# dimmer.net
KiCad netlist of a schematic drawn in EAGLE
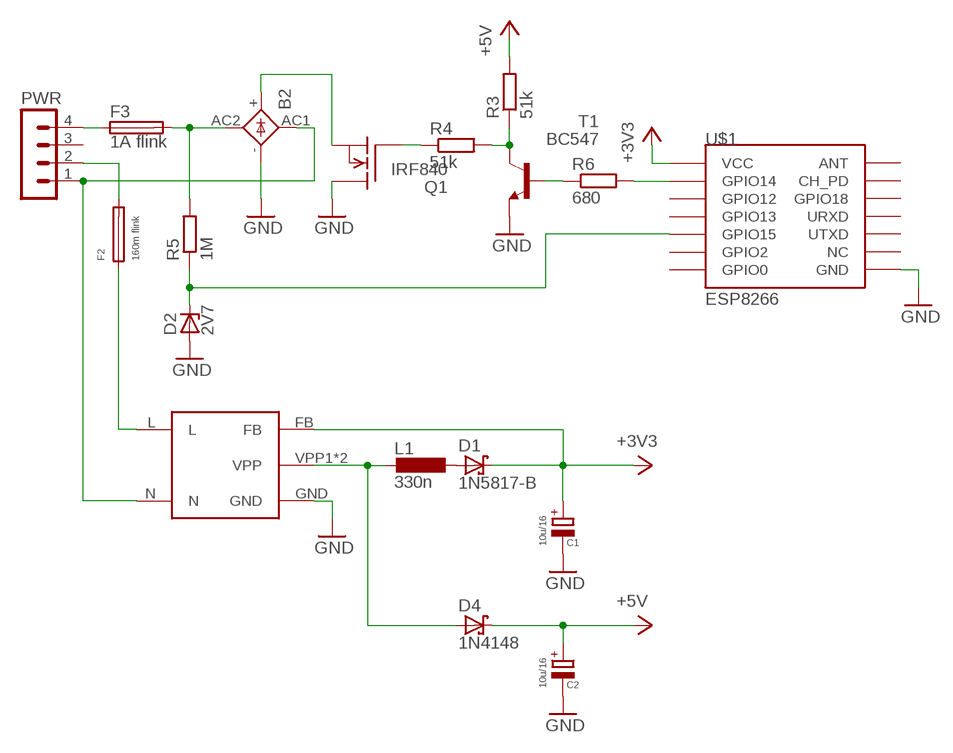
[diagram p0: schematic, sheet 1]

(export (version "E")
  (design (tool "Eeschema 10.0.6"))
  (components
    (comp (ref "B2")
      (value "2KBP")
      (footprint "eagle-import:2KBP")
      (libsource (lib "eagle-import") (part "2KBP"))
    )
    (comp (ref "C1")
      (value "10u/16")
      (footprint "eagle-import:E2,5-6")
      (libsource (lib "eagle-import") (part "CPOL-EUE2.5-6"))
    )
    (comp (ref "C2")
      (value "10u/16")
      (footprint "eagle-import:E2,5-6")
      (libsource (lib "eagle-import") (part "CPOL-EUE2.5-6"))
    )
    (comp (ref "D1")
      (value "1N5817-B")
      (footprint "eagle-import:DO41-7.6")
      (libsource (lib "eagle-import") (part "1N5817-B"))
    )
    (comp (ref "D2")
      (value "2V7")
      (footprint "eagle-import:DO34Z7")
      (libsource (lib "eagle-import") (part "ZENER-DIODEDO34-7"))
    )
    (comp (ref "D4")
      (value "1N4148")
      (footprint "eagle-import:DO41-7.6")
      (libsource (lib "eagle-import") (part "1N5817-B"))
    )
    (comp (ref "F2")
      (value "160m flink")
      (footprint "eagle-import:19560")
      (fields (field (name "MPN") "56000001009"))
      (libsource (lib "eagle-import") (part "19560"))
    )
    (comp (ref "F3")
      (value "1A flink")
      (footprint "eagle-import:SHK20L")
      (libsource (lib "eagle-import") (part "FUSESHK20L"))
    )
    (comp (ref "L1")
      (value "330n")
      (footprint "eagle-import:0204_5")
      (libsource (lib "eagle-import") (part "L-EU0204/5"))
    )
    (comp (ref "PWR")
      (value "MA04-1")
      (footprint "eagle-import:MA04-1")
      (libsource (lib "eagle-import") (part "MA04-1"))
    )
    (comp (ref "Q1")
      (value "IRF840")
      (footprint "eagle-import:TO220")
      (libsource (lib "eagle-import") (part "IRF840"))
    )
    (comp (ref "R3")
      (value "51k")
      (footprint "eagle-import:0207_10")
      (libsource (lib "eagle-import") (part "R-EU_0207/10"))
    )
    (comp (ref "R4")
      (value "51k")
      (footprint "eagle-import:0207_10")
      (libsource (lib "eagle-import") (part "R-EU_0207/10"))
    )
    (comp (ref "R5")
      (value "1M")
      (footprint "eagle-import:0207_12")
      (libsource (lib "eagle-import") (part "R-EU_0207/12"))
    )
    (comp (ref "R6")
      (value "680")
      (footprint "eagle-import:0207_10")
      (libsource (lib "eagle-import") (part "R-EU_0207/10"))
    )
    (comp (ref "T1")
      (value "BC547")
      (footprint "eagle-import:TO92")
      (libsource (lib "eagle-import") (part "BC547"))
    )
    (comp (ref "U$1")
      (value "ESP8266")
      (footprint "eagle-import:ESP-03")
      (libsource (lib "eagle-import") (part "ESP8266"))
    )
    (comp (ref "U$2")
      (value "SMPS")
      (footprint "eagle-import:SMPS")
      (libsource (lib "eagle-import") (part "SMPS"))
    )
  )
  (nets
    (net (code "1") (name "+3V3") (class "Default")
      (node (ref "C1") (pin "+") (pinfunction "+_+") (pintype "passive"))
      (node (ref "D1") (pin "C") (pinfunction "C_C") (pintype "passive"))
      (node (ref "U$1") (pin "VCC") (pinfunction "VCC_VCC") (pintype "bidirectional"))
      (node (ref "U$2") (pin "FB") (pinfunction "FB_FB") (pintype "bidirectional"))
    )
    (net (code "2") (name "+5V") (class "Default")
      (node (ref "C2") (pin "+") (pinfunction "+_+") (pintype "passive"))
      (node (ref "D4") (pin "C") (pinfunction "C_C") (pintype "passive"))
      (node (ref "R3") (pin "2") (pinfunction "2_2") (pintype "passive"))
    )
    (net (code "3") (name "GND") (class "Default")
      (node (ref "B2") (pin "-") (pinfunction "-_-") (pintype "passive"))
      (node (ref "C1") (pin "-") (pinfunction "-_-") (pintype "passive"))
      (node (ref "C2") (pin "-") (pinfunction "-_-") (pintype "passive"))
      (node (ref "D2") (pin "A") (pinfunction "A_A") (pintype "passive"))
      (node (ref "Q1") (pin "2") (pinfunction "D_2") (pintype "passive"))
      (node (ref "T1") (pin "1") (pinfunction "E_1") (pintype "passive"))
      (node (ref "U$1") (pin "GND") (pinfunction "GND_GND") (pintype "bidirectional"))
      (node (ref "U$2") (pin "GND") (pinfunction "GND_GND") (pintype "bidirectional"))
    )
    (net (code "4") (name "Net-(B2-PadAC1)") (class "Default")
      (node (ref "B2") (pin "AC1") (pinfunction "AC1_AC1") (pintype "passive"))
      (node (ref "PWR") (pin "1") (pinfunction "1_1") (pintype "passive"))
      (node (ref "U$2") (pin "N") (pinfunction "N_N") (pintype "bidirectional"))
    )
    (net (code "5") (name "Net-(D1-PadA)") (class "Default")
      (node (ref "D1") (pin "A") (pinfunction "A_A") (pintype "passive"))
      (node (ref "L1") (pin "1") (pinfunction "1_1") (pintype "passive"))
    )
    (net (code "6") (name "Net-(D2-PadC)") (class "Default")
      (node (ref "D2") (pin "C") (pinfunction "C_C") (pintype "passive"))
      (node (ref "R5") (pin "1") (pinfunction "1_1") (pintype "passive"))
      (node (ref "U$1") (pin "GPIO15") (pinfunction "GPIO15_GPIO15") (pintype "bidirectional"))
    )
    (net (code "7") (name "Net-(D4-PadA)") (class "Default")
      (node (ref "D4") (pin "A") (pinfunction "A_A") (pintype "passive"))
      (node (ref "L1") (pin "2") (pinfunction "2_2") (pintype "passive"))
      (node (ref "U$2") (pin "VPP1") (pinfunction "VPP_VPP1") (pintype "bidirectional"))
      (node (ref "U$2") (pin "VPP2") (pinfunction "VPP_VPP2") (pintype "bidirectional"))
    )
    (net (code "8") (name "Net-(F2-Pad1)") (class "Default")
      (node (ref "F2") (pin "1") (pinfunction "1_1") (pintype "passive"))
      (node (ref "U$2") (pin "L") (pinfunction "L_L") (pintype "bidirectional"))
    )
    (net (code "9") (name "Net-(F2-Pad2)") (class "Default")
      (node (ref "F2") (pin "2") (pinfunction "2_2") (pintype "passive"))
      (node (ref "PWR") (pin "2") (pinfunction "2_2") (pintype "passive"))
    )
    (net (code "10") (name "Net-(F3-1)") (class "Default")
      (node (ref "F3") (pin "1A") (pinfunction "1_1A") (pintype "passive"))
      (node (ref "PWR") (pin "4") (pinfunction "4_4") (pintype "passive"))
    )
    (net (code "11") (name "Net-(F3-2)") (class "Default")
      (node (ref "B2") (pin "AC2") (pinfunction "AC2_AC2") (pintype "passive"))
      (node (ref "F3") (pin "2A") (pinfunction "2_2A") (pintype "passive"))
      (node (ref "R5") (pin "2") (pinfunction "2_2") (pintype "passive"))
    )
    (net (code "12") (name "Net-(Q1-G)") (class "Default")
      (node (ref "Q1") (pin "1") (pinfunction "G_1") (pintype "passive"))
      (node (ref "R4") (pin "1") (pinfunction "1_1") (pintype "passive"))
    )
    (net (code "13") (name "Net-(Q1-S)") (class "Default")
      (node (ref "B2") (pin "+") (pinfunction "+_+") (pintype "passive"))
      (node (ref "Q1") (pin "3") (pinfunction "S_3") (pintype "passive"))
    )
    (net (code "14") (name "Net-(R6-Pad2)") (class "Default")
      (node (ref "R6") (pin "2") (pinfunction "2_2") (pintype "passive"))
      (node (ref "U$1") (pin "GPIO14") (pinfunction "GPIO14_GPIO14") (pintype "bidirectional"))
    )
    (net (code "15") (name "Net-(T1-B)") (class "Default")
      (node (ref "R6") (pin "1") (pinfunction "1_1") (pintype "passive"))
      (node (ref "T1") (pin "2") (pinfunction "B_2") (pintype "passive"))
    )
    (net (code "16") (name "Net-(T1-C)") (class "Default")
      (node (ref "R3") (pin "1") (pinfunction "1_1") (pintype "passive"))
      (node (ref "R4") (pin "2") (pinfunction "2_2") (pintype "passive"))
      (node (ref "T1") (pin "3") (pinfunction "C_3") (pintype "passive"))
    )
    (net (code "17") (name "unconnected-(PWR-Pad3)") (class "Default")
      (node (ref "PWR") (pin "3") (pinfunction "3_3") (pintype "passive"))
    )
    (net (code "18") (name "unconnected-(U$1-PadANT)") (class "Default")
      (node (ref "U$1") (pin "ANT") (pinfunction "ANT_ANT") (pintype "bidirectional"))
    )
    (net (code "19") (name "unconnected-(U$1-PadCH_PD)") (class "Default")
      (node (ref "U$1") (pin "CH_PD") (pinfunction "CH_PD_CH_PD") (pintype "bidirectional"))
    )
    (net (code "20") (name "unconnected-(U$1-PadGPIO0)") (class "Default")
      (node (ref "U$1") (pin "GPIO0") (pinfunction "GPIO0_GPIO0") (pintype "bidirectional"))
    )
    (net (code "21") (name "unconnected-(U$1-PadGPIO2)") (class "Default")
      (node (ref "U$1") (pin "GPIO2") (pinfunction "GPIO2_GPIO2") (pintype "bidirectional"))
    )
    (net (code "22") (name "unconnected-(U$1-PadGPIO12)") (class "Default")
      (node (ref "U$1") (pin "GPIO12") (pinfunction "GPIO12_GPIO12") (pintype "bidirectional"))
    )
    (net (code "23") (name "unconnected-(U$1-PadGPIO13)") (class "Default")
      (node (ref "U$1") (pin "GPIO13") (pinfunction "GPIO13_GPIO13") (pintype "bidirectional"))
    )
    (net (code "24") (name "unconnected-(U$1-PadGPIO18)") (class "Default")
      (node (ref "U$1") (pin "GPIO18") (pinfunction "GPIO18_GPIO18") (pintype "bidirectional"))
    )
    (net (code "25") (name "unconnected-(U$1-PadNC)") (class "Default")
      (node (ref "U$1") (pin "NC") (pinfunction "NC_NC") (pintype "bidirectional"))
    )
    (net (code "26") (name "unconnected-(U$1-PadURXD)") (class "Default")
      (node (ref "U$1") (pin "URXD") (pinfunction "URXD_URXD") (pintype "bidirectional"))
    )
    (net (code "27") (name "unconnected-(U$1-PadUTXD)") (class "Default")
      (node (ref "U$1") (pin "UTXD") (pinfunction "UTXD_UTXD") (pintype "bidirectional"))
    )
  )
)
